# 8x8_LED_Anode_Driver_V3.net
KiCad netlist of a schematic drawn in EAGLE
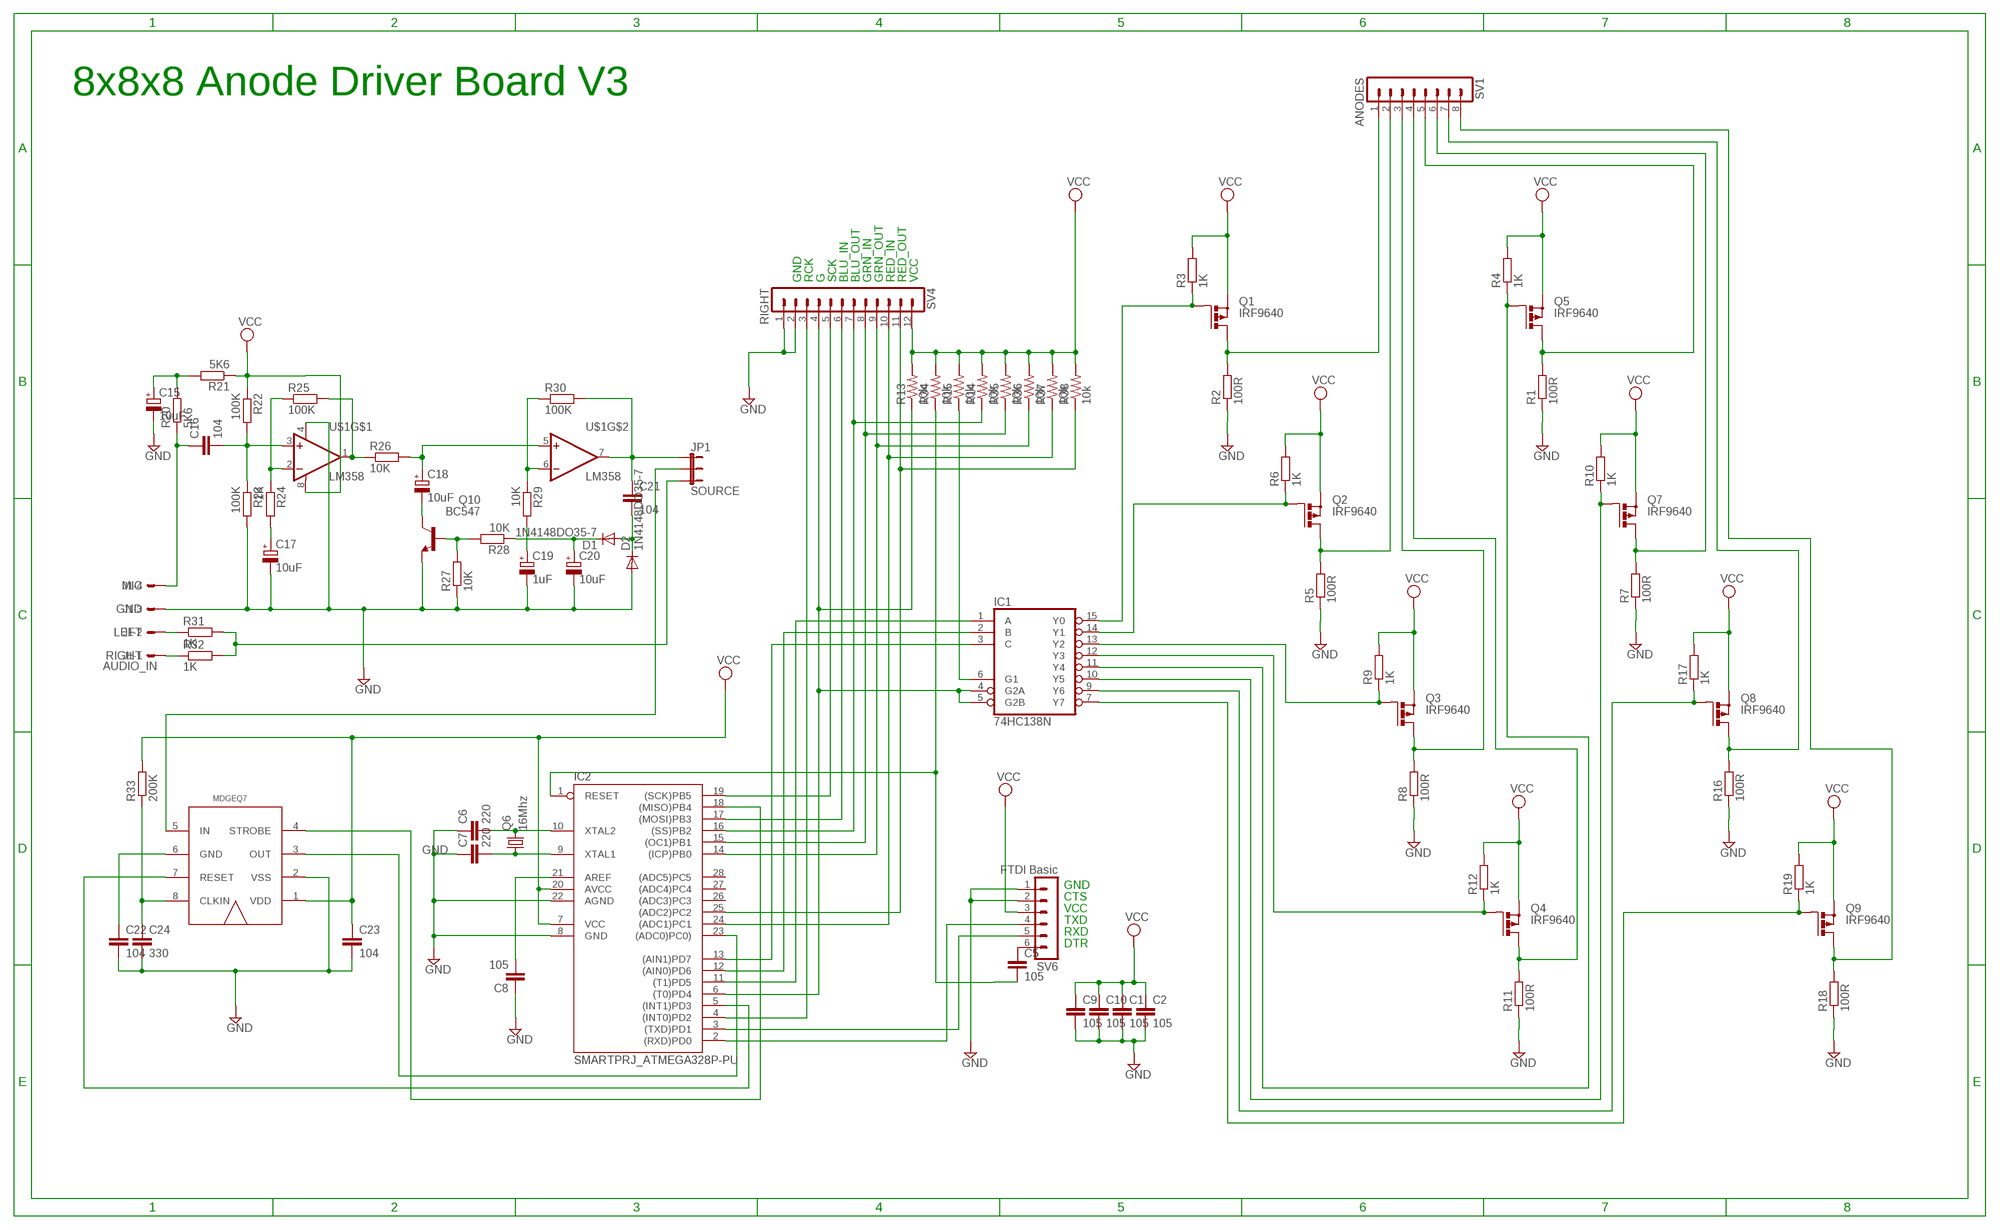
[diagram p0: schematic, sheet 1]

(export (version "E")
  (design (tool "Eeschema 10.0.6"))
  (components
    (comp (ref "C1")
      (value "105")
      (footprint "eagle-import:C025-030X050")
      (libsource (lib "eagle-import") (part "C-EU025-030X050"))
    )
    (comp (ref "C2")
      (value "105")
      (footprint "eagle-import:C025-030X050")
      (libsource (lib "eagle-import") (part "C-EU025-030X050"))
    )
    (comp (ref "C5")
      (value "105")
      (footprint "eagle-import:C050-025X075")
      (libsource (lib "eagle-import") (part "C-EU050-025X075"))
    )
    (comp (ref "C6")
      (value "220")
      (footprint "eagle-import:C050-025X075")
      (libsource (lib "eagle-import") (part "C-EU050-025X075"))
    )
    (comp (ref "C7")
      (value "220")
      (footprint "eagle-import:C050-025X075")
      (libsource (lib "eagle-import") (part "C-EU050-025X075"))
    )
    (comp (ref "C8")
      (value "105")
      (footprint "eagle-import:C025-025X050")
      (libsource (lib "eagle-import") (part "C-EU025-025X050"))
    )
    (comp (ref "C9")
      (value "105")
      (footprint "eagle-import:C025-025X050")
      (libsource (lib "eagle-import") (part "C-EU025-025X050"))
    )
    (comp (ref "C10")
      (value "105")
      (footprint "eagle-import:C025-030X050")
      (libsource (lib "eagle-import") (part "C-EU025-030X050"))
    )
    (comp (ref "C15")
      (value "10uF")
      (footprint "eagle-import:E2,5-5")
      (libsource (lib "eagle-import") (part "CPOL-EUE2.5-5"))
    )
    (comp (ref "C16")
      (value "104")
      (footprint "eagle-import:C050-030X075")
      (libsource (lib "eagle-import") (part "C-EU050-030X075"))
    )
    (comp (ref "C17")
      (value "10uF")
      (footprint "eagle-import:E2,5-5")
      (libsource (lib "eagle-import") (part "CPOL-EUE2.5-5"))
    )
    (comp (ref "C18")
      (value "10uF")
      (footprint "eagle-import:E2,5-5")
      (libsource (lib "eagle-import") (part "CPOL-EUE2.5-5"))
    )
    (comp (ref "C19")
      (value "1uF")
      (footprint "eagle-import:E2,5-5")
      (libsource (lib "eagle-import") (part "CPOL-EUE2.5-5"))
    )
    (comp (ref "C20")
      (value "10uF")
      (footprint "eagle-import:E2,5-5")
      (libsource (lib "eagle-import") (part "CPOL-EUE2.5-5"))
    )
    (comp (ref "C21")
      (value "104")
      (footprint "eagle-import:C050-030X075")
      (libsource (lib "eagle-import") (part "C-EU050-030X075"))
    )
    (comp (ref "C22")
      (value "104")
      (footprint "eagle-import:C025-030X050")
      (libsource (lib "eagle-import") (part "C-EU025-030X050"))
    )
    (comp (ref "C23")
      (value "104")
      (footprint "eagle-import:C025-030X050")
      (libsource (lib "eagle-import") (part "C-EU025-030X050"))
    )
    (comp (ref "C24")
      (value "330")
      (footprint "eagle-import:C050-030X075")
      (libsource (lib "eagle-import") (part "C-EU050-030X075"))
    )
    (comp (ref "D1")
      (value "1N4148DO35-7")
      (footprint "eagle-import:DO35-7")
      (libsource (lib "eagle-import") (part "1N4148DO35-7"))
    )
    (comp (ref "D2")
      (value "1N4148DO35-7")
      (footprint "eagle-import:DO35-7")
      (libsource (lib "eagle-import") (part "1N4148DO35-7"))
    )
    (comp (ref "IC1")
      (value "74HC138N")
      (footprint "eagle-import:DIL16")
      (libsource (lib "eagle-import") (part "74138NHC"))
    )
    (comp (ref "IC2")
      (value "SMARTPRJ_ATMEGA328P-PU")
      (footprint "eagle-import:SMARTPRJ_DIL28-3")
      (libsource (lib "eagle-import") (part "SMARTPRJ_ATMEGA328P-PU"))
    )
    (comp (ref "J1")
      (value "AUDIO_IN")
      (footprint "eagle-import:7395-04")
      (libsource (lib "eagle-import") (part "22-?-0405-7048"))
    )
    (comp (ref "JP1")
      (value "SOURCE")
      (footprint "eagle-import:1X03")
      (libsource (lib "eagle-import") (part "JUMPER-3PTH"))
    )
    (comp (ref "Q1")
      (value "IRF9640")
      (footprint "eagle-import:TO220BH_NO_HOLE")
      (libsource (lib "eagle-import") (part "PMOSFET_PTO220BH_NH"))
    )
    (comp (ref "Q2")
      (value "IRF9640")
      (footprint "eagle-import:TO220BH_NO_HOLE")
      (libsource (lib "eagle-import") (part "PMOSFET_PTO220BH_NH"))
    )
    (comp (ref "Q3")
      (value "IRF9640")
      (footprint "eagle-import:TO220BH_NO_HOLE")
      (libsource (lib "eagle-import") (part "PMOSFET_PTO220BH_NH"))
    )
    (comp (ref "Q4")
      (value "IRF9640")
      (footprint "eagle-import:TO220BH_NO_HOLE")
      (libsource (lib "eagle-import") (part "PMOSFET_PTO220BH_NH"))
    )
    (comp (ref "Q5")
      (value "IRF9640")
      (footprint "eagle-import:TO220BH_NO_HOLE")
      (libsource (lib "eagle-import") (part "PMOSFET_PTO220BH_NH"))
    )
    (comp (ref "Q6")
      (value "16Mhz")
      (footprint "eagle-import:HC49_S")
      (libsource (lib "eagle-import") (part "CRYSTALHC49S"))
    )
    (comp (ref "Q7")
      (value "IRF9640")
      (footprint "eagle-import:TO220BH_NO_HOLE")
      (libsource (lib "eagle-import") (part "PMOSFET_PTO220BH_NH"))
    )
    (comp (ref "Q8")
      (value "IRF9640")
      (footprint "eagle-import:TO220BH_NO_HOLE")
      (libsource (lib "eagle-import") (part "PMOSFET_PTO220BH_NH"))
    )
    (comp (ref "Q9")
      (value "IRF9640")
      (footprint "eagle-import:TO220BH_NO_HOLE")
      (libsource (lib "eagle-import") (part "PMOSFET_PTO220BH_NH"))
    )
    (comp (ref "Q10")
      (value "BC547")
      (footprint "eagle-import:TO92")
      (libsource (lib "eagle-import") (part "BC547"))
    )
    (comp (ref "R1")
      (value "100R")
      (footprint "eagle-import:0207_10")
      (libsource (lib "eagle-import") (part "R-EU_0207/10"))
    )
    (comp (ref "R2")
      (value "100R")
      (footprint "eagle-import:0207_10")
      (libsource (lib "eagle-import") (part "R-EU_0207/10"))
    )
    (comp (ref "R3")
      (value "1K")
      (footprint "eagle-import:0207_10")
      (libsource (lib "eagle-import") (part "R-EU_0207/10"))
    )
    (comp (ref "R4")
      (value "1K")
      (footprint "eagle-import:0207_10")
      (libsource (lib "eagle-import") (part "R-EU_0207/10"))
    )
    (comp (ref "R5")
      (value "100R")
      (footprint "eagle-import:0207_10")
      (libsource (lib "eagle-import") (part "R-EU_0207/10"))
    )
    (comp (ref "R6")
      (value "1K")
      (footprint "eagle-import:0207_10")
      (libsource (lib "eagle-import") (part "R-EU_0207/10"))
    )
    (comp (ref "R7")
      (value "100R")
      (footprint "eagle-import:0207_10")
      (libsource (lib "eagle-import") (part "R-EU_0207/10"))
    )
    (comp (ref "R8")
      (value "100R")
      (footprint "eagle-import:0207_10")
      (libsource (lib "eagle-import") (part "R-EU_0207/10"))
    )
    (comp (ref "R9")
      (value "1K")
      (footprint "eagle-import:0207_10")
      (libsource (lib "eagle-import") (part "R-EU_0207/10"))
    )
    (comp (ref "R10")
      (value "1K")
      (footprint "eagle-import:0207_10")
      (libsource (lib "eagle-import") (part "R-EU_0207/10"))
    )
    (comp (ref "R11")
      (value "100R")
      (footprint "eagle-import:0207_10")
      (libsource (lib "eagle-import") (part "R-EU_0207/10"))
    )
    (comp (ref "R12")
      (value "1K")
      (footprint "eagle-import:0207_10")
      (libsource (lib "eagle-import") (part "R-EU_0207/10"))
    )
    (comp (ref "R13")
      (value "10k")
      (footprint "eagle-import:0207_10")
      (libsource (lib "eagle-import") (part "R-US_0207/10"))
    )
    (comp (ref "R14")
      (value "10k")
      (footprint "eagle-import:0207_10")
      (libsource (lib "eagle-import") (part "R-US_0207/10"))
    )
    (comp (ref "R15")
      (value "10k")
      (footprint "eagle-import:0207_10")
      (libsource (lib "eagle-import") (part "R-US_0207/10"))
    )
    (comp (ref "R16")
      (value "100R")
      (footprint "eagle-import:0207_10")
      (libsource (lib "eagle-import") (part "R-EU_0207/10"))
    )
    (comp (ref "R17")
      (value "1K")
      (footprint "eagle-import:0207_10")
      (libsource (lib "eagle-import") (part "R-EU_0207/10"))
    )
    (comp (ref "R18")
      (value "100R")
      (footprint "eagle-import:0207_10")
      (libsource (lib "eagle-import") (part "R-EU_0207/10"))
    )
    (comp (ref "R19")
      (value "1K")
      (footprint "eagle-import:0207_10")
      (libsource (lib "eagle-import") (part "R-EU_0207/10"))
    )
    (comp (ref "R20")
      (value "5K6")
      (footprint "eagle-import:0207_10")
      (libsource (lib "eagle-import") (part "R-EU_0207/10"))
    )
    (comp (ref "R21")
      (value "5K6")
      (footprint "eagle-import:0207_10")
      (libsource (lib "eagle-import") (part "R-EU_0207/10"))
    )
    (comp (ref "R22")
      (value "100K")
      (footprint "eagle-import:0207_10")
      (libsource (lib "eagle-import") (part "R-EU_0207/10"))
    )
    (comp (ref "R23")
      (value "100K")
      (footprint "eagle-import:0207_10")
      (libsource (lib "eagle-import") (part "R-EU_0207/10"))
    )
    (comp (ref "R24")
      (value "1K")
      (footprint "eagle-import:0207_10")
      (libsource (lib "eagle-import") (part "R-EU_0207/10"))
    )
    (comp (ref "R25")
      (value "100K")
      (footprint "eagle-import:0207_10")
      (libsource (lib "eagle-import") (part "R-EU_0207/10"))
    )
    (comp (ref "R26")
      (value "10K")
      (footprint "eagle-import:0207_10")
      (libsource (lib "eagle-import") (part "R-EU_0207/10"))
    )
    (comp (ref "R27")
      (value "10K")
      (footprint "eagle-import:0207_10")
      (libsource (lib "eagle-import") (part "R-EU_0207/10"))
    )
    (comp (ref "R28")
      (value "10K")
      (footprint "eagle-import:0207_10")
      (libsource (lib "eagle-import") (part "R-EU_0207/10"))
    )
    (comp (ref "R29")
      (value "10K")
      (footprint "eagle-import:0207_10")
      (libsource (lib "eagle-import") (part "R-EU_0207/10"))
    )
    (comp (ref "R30")
      (value "100K")
      (footprint "eagle-import:0207_10")
      (libsource (lib "eagle-import") (part "R-EU_0207/10"))
    )
    (comp (ref "R31")
      (value "1K")
      (footprint "eagle-import:0207_10")
      (libsource (lib "eagle-import") (part "R-EU_0207/10"))
    )
    (comp (ref "R32")
      (value "1K")
      (footprint "eagle-import:0207_10")
      (libsource (lib "eagle-import") (part "R-EU_0207/10"))
    )
    (comp (ref "R33")
      (value "200K")
      (footprint "eagle-import:0207_10")
      (libsource (lib "eagle-import") (part "R-EU_0207/10"))
    )
    (comp (ref "R34")
      (value "10k")
      (footprint "eagle-import:0207_10")
      (libsource (lib "eagle-import") (part "R-US_0207/10"))
    )
    (comp (ref "R35")
      (value "10k")
      (footprint "eagle-import:0207_10")
      (libsource (lib "eagle-import") (part "R-US_0207/10"))
    )
    (comp (ref "R36")
      (value "10k")
      (footprint "eagle-import:0207_10")
      (libsource (lib "eagle-import") (part "R-US_0207/10"))
    )
    (comp (ref "R37")
      (value "10k")
      (footprint "eagle-import:0207_10")
      (libsource (lib "eagle-import") (part "R-US_0207/10"))
    )
    (comp (ref "R38")
      (value "10k")
      (footprint "eagle-import:0207_10")
      (libsource (lib "eagle-import") (part "R-US_0207/10"))
    )
    (comp (ref "SV1")
      (value "ANODES")
      (footprint "eagle-import:MA08-1W")
      (libsource (lib "eagle-import") (part "MA08-1W"))
    )
    (comp (ref "SV4")
      (value "RIGHT")
      (footprint "eagle-import:MA12-1W")
      (libsource (lib "eagle-import") (part "MA12-1W"))
    )
    (comp (ref "SV6")
      (value "FTDI Basic")
      (footprint "eagle-import:MA06-1")
      (libsource (lib "eagle-import") (part "MA06-1"))
    )
    (comp (ref "U$1")
      (value "LM358")
      (footprint "eagle-import:DIP08")
      (libsource (lib "eagle-import") (part "LM358"))
    )
    (comp (ref "U$2")
      (value "MSGEQ7")
      (footprint "eagle-import:DIL08")
      (libsource (lib "eagle-import") (part "MSGEQ7"))
    )
  )
  (nets
    (net (code "1") (name "GND") (class "Default")
      (node (ref "C1") (pin "2") (pinfunction "2_2") (pintype "passive"))
      (node (ref "C10") (pin "2") (pinfunction "2_2") (pintype "passive"))
      (node (ref "C15") (pin "-") (pinfunction "-_-") (pintype "passive"))
      (node (ref "C17") (pin "-") (pinfunction "-_-") (pintype "passive"))
      (node (ref "C19") (pin "-") (pinfunction "-_-") (pintype "passive"))
      (node (ref "C2") (pin "2") (pinfunction "2_2") (pintype "passive"))
      (node (ref "C20") (pin "-") (pinfunction "-_-") (pintype "passive"))
      (node (ref "C22") (pin "2") (pinfunction "2_2") (pintype "passive"))
      (node (ref "C23") (pin "2") (pinfunction "2_2") (pintype "passive"))
      (node (ref "C24") (pin "2") (pinfunction "2_2") (pintype "passive"))
      (node (ref "C6") (pin "1") (pinfunction "1_1") (pintype "passive"))
      (node (ref "C7") (pin "1") (pinfunction "1_1") (pintype "passive"))
      (node (ref "C8") (pin "1") (pinfunction "1_1") (pintype "passive"))
      (node (ref "C9") (pin "2") (pinfunction "2_2") (pintype "passive"))
      (node (ref "D2") (pin "A") (pinfunction "A_A") (pintype "passive"))
      (node (ref "IC2") (pin "22") (pinfunction "AGND_22") (pintype "power_in"))
      (node (ref "IC2") (pin "8") (pinfunction "GND_8") (pintype "power_in"))
      (node (ref "J1") (pin "3") (pinfunction "S_3") (pintype "passive"))
      (node (ref "Q10") (pin "1") (pinfunction "E_1") (pintype "passive"))
      (node (ref "R1") (pin "1") (pinfunction "1_1") (pintype "passive"))
      (node (ref "R11") (pin "1") (pinfunction "1_1") (pintype "passive"))
      (node (ref "R16") (pin "1") (pinfunction "1_1") (pintype "passive"))
      (node (ref "R18") (pin "1") (pinfunction "1_1") (pintype "passive"))
      (node (ref "R2") (pin "1") (pinfunction "1_1") (pintype "passive"))
      (node (ref "R23") (pin "2") (pinfunction "2_2") (pintype "passive"))
      (node (ref "R27") (pin "1") (pinfunction "1_1") (pintype "passive"))
      (node (ref "R5") (pin "1") (pinfunction "1_1") (pintype "passive"))
      (node (ref "R7") (pin "1") (pinfunction "1_1") (pintype "passive"))
      (node (ref "R8") (pin "1") (pinfunction "1_1") (pintype "passive"))
      (node (ref "SV4") (pin "1") (pinfunction "1_1") (pintype "passive"))
      (node (ref "SV4") (pin "2") (pinfunction "2_2") (pintype "passive"))
      (node (ref "SV6") (pin "1") (pinfunction "1_1") (pintype "passive"))
      (node (ref "SV6") (pin "2") (pinfunction "2_2") (pintype "passive"))
      (node (ref "U$1") (pin "4") (pinfunction "V-_4") (pintype "power_in"))
      (node (ref "U$2") (pin "2") (pinfunction "VSS_2") (pintype "power_in"))
    )
    (net (code "2") (name "Net-(C5-Pad1)") (class "Default")
      (node (ref "C5") (pin "1") (pinfunction "1_1") (pintype "passive"))
      (node (ref "SV6") (pin "6") (pinfunction "6_6") (pintype "passive"))
    )
    (net (code "3") (name "Net-(C15-Pad+)") (class "Default")
      (node (ref "C15") (pin "+") (pinfunction "+_+") (pintype "passive"))
      (node (ref "R20") (pin "2") (pinfunction "2_2") (pintype "passive"))
      (node (ref "R21") (pin "2") (pinfunction "2_2") (pintype "passive"))
    )
    (net (code "4") (name "Net-(C17-Pad+)") (class "Default")
      (node (ref "C17") (pin "+") (pinfunction "+_+") (pintype "passive"))
      (node (ref "R24") (pin "2") (pinfunction "2_2") (pintype "passive"))
    )
    (net (code "5") (name "Net-(C19-Pad+)") (class "Default")
      (node (ref "C19") (pin "+") (pinfunction "+_+") (pintype "passive"))
      (node (ref "R29") (pin "2") (pinfunction "2_2") (pintype "passive"))
    )
    (net (code "6") (name "Net-(C20-Pad+)") (class "Default")
      (node (ref "C20") (pin "+") (pinfunction "+_+") (pintype "passive"))
      (node (ref "D1") (pin "C") (pinfunction "C_C") (pintype "passive"))
      (node (ref "R28") (pin "1") (pinfunction "1_1") (pintype "passive"))
    )
    (net (code "7") (name "Net-(C21-Pad2)") (class "Default")
      (node (ref "C21") (pin "2") (pinfunction "2_2") (pintype "passive"))
      (node (ref "D1") (pin "A") (pinfunction "A_A") (pintype "passive"))
      (node (ref "D2") (pin "C") (pinfunction "C_C") (pintype "passive"))
    )
    (net (code "8") (name "Net-(IC1A-A)") (class "Default")
      (node (ref "IC1") (pin "1") (pinfunction "A_1") (pintype "input"))
      (node (ref "IC2") (pin "11") (pinfunction "(T1)PD5_11") (pintype "bidirectional"))
    )
    (net (code "9") (name "Net-(IC1A-B)") (class "Default")
      (node (ref "IC1") (pin "2") (pinfunction "B_2") (pintype "input"))
      (node (ref "IC2") (pin "12") (pinfunction "(AIN0)PD6_12") (pintype "bidirectional"))
    )
    (net (code "10") (name "Net-(IC1A-C)") (class "Default")
      (node (ref "IC1") (pin "3") (pinfunction "C_3") (pintype "input"))
      (node (ref "IC2") (pin "13") (pinfunction "(AIN1)PD7_13") (pintype "bidirectional"))
    )
    (net (code "11") (name "Net-(IC1A-G1)") (class "Default")
      (node (ref "IC1") (pin "6") (pinfunction "G1_6") (pintype "input"))
      (node (ref "R15") (pin "1") (pinfunction "1_1") (pintype "passive"))
    )
    (net (code "12") (name "Net-(IC1A-G2A)") (class "Default")
      (node (ref "IC1") (pin "4") (pinfunction "G2A_4") (pintype "input"))
      (node (ref "IC1") (pin "5") (pinfunction "G2B_5") (pintype "input"))
      (node (ref "IC2") (pin "6") (pinfunction "(T0)PD4_6") (pintype "bidirectional"))
      (node (ref "R13") (pin "1") (pinfunction "1_1") (pintype "passive"))
      (node (ref "SV4") (pin "4") (pinfunction "4_4") (pintype "passive"))
    )
    (net (code "13") (name "Net-(IC1A-Y0)") (class "Default")
      (node (ref "IC1") (pin "15") (pinfunction "Y0_15") (pintype "output"))
      (node (ref "Q1") (pin "G") (pinfunction "G_G") (pintype "passive"))
      (node (ref "R3") (pin "1") (pinfunction "1_1") (pintype "passive"))
    )
    (net (code "14") (name "Net-(IC1A-Y1)") (class "Default")
      (node (ref "IC1") (pin "14") (pinfunction "Y1_14") (pintype "output"))
      (node (ref "Q2") (pin "G") (pinfunction "G_G") (pintype "passive"))
      (node (ref "R6") (pin "1") (pinfunction "1_1") (pintype "passive"))
    )
    (net (code "15") (name "Net-(IC1A-Y2)") (class "Default")
      (node (ref "IC1") (pin "13") (pinfunction "Y2_13") (pintype "output"))
      (node (ref "Q3") (pin "G") (pinfunction "G_G") (pintype "passive"))
      (node (ref "R9") (pin "1") (pinfunction "1_1") (pintype "passive"))
    )
    (net (code "16") (name "Net-(IC1A-Y3)") (class "Default")
      (node (ref "IC1") (pin "12") (pinfunction "Y3_12") (pintype "output"))
      (node (ref "Q4") (pin "G") (pinfunction "G_G") (pintype "passive"))
      (node (ref "R12") (pin "1") (pinfunction "1_1") (pintype "passive"))
    )
    (net (code "17") (name "Net-(IC1A-Y4)") (class "Default")
      (node (ref "IC1") (pin "11") (pinfunction "Y4_11") (pintype "output"))
      (node (ref "Q5") (pin "G") (pinfunction "G_G") (pintype "passive"))
      (node (ref "R4") (pin "1") (pinfunction "1_1") (pintype "passive"))
    )
    (net (code "18") (name "Net-(IC1A-Y5)") (class "Default")
      (node (ref "IC1") (pin "10") (pinfunction "Y5_10") (pintype "output"))
      (node (ref "Q7") (pin "G") (pinfunction "G_G") (pintype "passive"))
      (node (ref "R10") (pin "1") (pinfunction "1_1") (pintype "passive"))
    )
    (net (code "19") (name "Net-(IC1A-Y6)") (class "Default")
      (node (ref "IC1") (pin "9") (pinfunction "Y6_9") (pintype "output"))
      (node (ref "Q8") (pin "G") (pinfunction "G_G") (pintype "passive"))
      (node (ref "R17") (pin "1") (pinfunction "1_1") (pintype "passive"))
    )
    (net (code "20") (name "Net-(IC1A-Y7)") (class "Default")
      (node (ref "IC1") (pin "7") (pinfunction "Y7_7") (pintype "output"))
      (node (ref "Q9") (pin "G") (pinfunction "G_G") (pintype "passive"))
      (node (ref "R19") (pin "1") (pinfunction "1_1") (pintype "passive"))
    )
    (net (code "21") (name "Net-(IC2-(ADC0)PC0))") (class "Default")
      (node (ref "IC2") (pin "23") (pinfunction "(ADC0)PC0)_23") (pintype "bidirectional"))
      (node (ref "U$2") (pin "3") (pinfunction "OUT_3") (pintype "output"))
    )
    (net (code "22") (name "Net-(IC2-(ADC1)PC1)") (class "Default")
      (node (ref "IC2") (pin "24") (pinfunction "(ADC1)PC1_24") (pintype "bidirectional"))
      (node (ref "R37") (pin "1") (pinfunction "1_1") (pintype "passive"))
      (node (ref "SV4") (pin "10") (pinfunction "10_10") (pintype "passive"))
    )
    (net (code "23") (name "Net-(IC2-(ADC2)PC2)") (class "Default")
      (node (ref "IC2") (pin "25") (pinfunction "(ADC2)PC2_25") (pintype "bidirectional"))
      (node (ref "R38") (pin "1") (pinfunction "1_1") (pintype "passive"))
      (node (ref "SV4") (pin "11") (pinfunction "11_11") (pintype "passive"))
    )
    (net (code "24") (name "Net-(IC2-(ICP)PB0)") (class "Default")
      (node (ref "IC2") (pin "14") (pinfunction "(ICP)PB0_14") (pintype "bidirectional"))
      (node (ref "R36") (pin "1") (pinfunction "1_1") (pintype "passive"))
      (node (ref "SV4") (pin "9") (pinfunction "9_9") (pintype "passive"))
    )
    (net (code "25") (name "Net-(IC2-(INT0)PD2)") (class "Default")
      (node (ref "IC2") (pin "4") (pinfunction "(INT0)PD2_4") (pintype "bidirectional"))
      (node (ref "SV4") (pin "3") (pinfunction "3_3") (pintype "passive"))
    )
    (net (code "26") (name "Net-(IC2-(INT1)PD3)") (class "Default")
      (node (ref "IC2") (pin "5") (pinfunction "(INT1)PD3_5") (pintype "bidirectional"))
      (node (ref "U$2") (pin "7") (pinfunction "RESET_7") (pintype "input"))
    )
    (net (code "27") (name "Net-(IC2-(MISO)PB4)") (class "Default")
      (node (ref "IC2") (pin "18") (pinfunction "(MISO)PB4_18") (pintype "bidirectional"))
      (node (ref "U$2") (pin "4") (pinfunction "STROBE_4") (pintype "input"))
    )
    (net (code "28") (name "Net-(IC2-(MOSI)PB3)") (class "Default")
      (node (ref "IC2") (pin "17") (pinfunction "(MOSI)PB3_17") (pintype "bidirectional"))
      (node (ref "SV4") (pin "6") (pinfunction "6_6") (pintype "passive"))
    )
    (net (code "29") (name "Net-(IC2-(OC1)PB1)") (class "Default")
      (node (ref "IC2") (pin "15") (pinfunction "(OC1)PB1_15") (pintype "bidirectional"))
      (node (ref "R35") (pin "1") (pinfunction "1_1") (pintype "passive"))
      (node (ref "SV4") (pin "8") (pinfunction "8_8") (pintype "passive"))
    )
    (net (code "30") (name "Net-(IC2-(RXD)PD0)") (class "Default")
      (node (ref "IC2") (pin "2") (pinfunction "(RXD)PD0_2") (pintype "bidirectional"))
      (node (ref "SV6") (pin "4") (pinfunction "4_4") (pintype "passive"))
    )
    (net (code "31") (name "Net-(IC2-(SCK)PB5)") (class "Default")
      (node (ref "IC2") (pin "19") (pinfunction "(SCK)PB5_19") (pintype "bidirectional"))
      (node (ref "SV4") (pin "5") (pinfunction "5_5") (pintype "passive"))
    )
    (net (code "32") (name "Net-(IC2-(SS)PB2)") (class "Default")
      (node (ref "IC2") (pin "16") (pinfunction "(SS)PB2_16") (pintype "bidirectional"))
      (node (ref "R14") (pin "1") (pinfunction "1_1") (pintype "passive"))
      (node (ref "SV4") (pin "7") (pinfunction "7_7") (pintype "passive"))
    )
    (net (code "33") (name "Net-(IC2-(TXD)PD1)") (class "Default")
      (node (ref "IC2") (pin "3") (pinfunction "(TXD)PD1_3") (pintype "bidirectional"))
      (node (ref "SV6") (pin "5") (pinfunction "5_5") (pintype "passive"))
    )
    (net (code "34") (name "Net-(IC2-AREF)") (class "Default")
      (node (ref "C8") (pin "2") (pinfunction "2_2") (pintype "passive"))
      (node (ref "IC2") (pin "21") (pinfunction "AREF_21") (pintype "passive"))
    )
    (net (code "35") (name "Net-(IC2-RESET)") (class "Default")
      (node (ref "C5") (pin "2") (pinfunction "2_2") (pintype "passive"))
      (node (ref "IC2") (pin "1") (pinfunction "RESET_1") (pintype "input"))
      (node (ref "R34") (pin "1") (pinfunction "1_1") (pintype "passive"))
    )
    (net (code "36") (name "Net-(IC2-XTAL1)") (class "Default")
      (node (ref "C7") (pin "2") (pinfunction "2_2") (pintype "passive"))
      (node (ref "IC2") (pin "9") (pinfunction "XTAL1_9") (pintype "bidirectional"))
      (node (ref "Q6") (pin "1") (pinfunction "1_1") (pintype "passive"))
    )
    (net (code "37") (name "Net-(IC2-XTAL2)") (class "Default")
      (node (ref "C6") (pin "2") (pinfunction "2_2") (pintype "passive"))
      (node (ref "IC2") (pin "10") (pinfunction "XTAL2_10") (pintype "bidirectional"))
      (node (ref "Q6") (pin "2") (pinfunction "2_2") (pintype "passive"))
    )
    (net (code "38") (name "Net-(J1A-S)") (class "Default")
      (node (ref "J1") (pin "1") (pinfunction "S_1") (pintype "passive"))
      (node (ref "R32") (pin "1") (pinfunction "1_1") (pintype "passive"))
    )
    (net (code "39") (name "Net-(J1B-S)") (class "Default")
      (node (ref "J1") (pin "2") (pinfunction "S_2") (pintype "passive"))
      (node (ref "R31") (pin "1") (pinfunction "1_1") (pintype "passive"))
    )
    (net (code "40") (name "Net-(J1D-S)") (class "Default")
      (node (ref "C16") (pin "1") (pinfunction "1_1") (pintype "passive"))
      (node (ref "J1") (pin "4") (pinfunction "S_4") (pintype "passive"))
      (node (ref "R20") (pin "1") (pinfunction "1_1") (pintype "passive"))
    )
    (net (code "41") (name "Net-(JP1-Pad3)") (class "Default")
      (node (ref "JP1") (pin "3") (pinfunction "3_3") (pintype "passive"))
      (node (ref "R31") (pin "2") (pinfunction "2_2") (pintype "passive"))
      (node (ref "R32") (pin "2") (pinfunction "2_2") (pintype "passive"))
    )
    (net (code "42") (name "Net-(Q1-PadD)") (class "Default")
      (node (ref "Q1") (pin "D") (pinfunction "D_D") (pintype "passive"))
      (node (ref "R2") (pin "2") (pinfunction "2_2") (pintype "passive"))
      (node (ref "SV1") (pin "1") (pinfunction "1_1") (pintype "passive"))
    )
    (net (code "43") (name "Net-(Q2-PadD)") (class "Default")
      (node (ref "Q2") (pin "D") (pinfunction "D_D") (pintype "passive"))
      (node (ref "R5") (pin "2") (pinfunction "2_2") (pintype "passive"))
      (node (ref "SV1") (pin "2") (pinfunction "2_2") (pintype "passive"))
    )
    (net (code "44") (name "Net-(Q3-PadD)") (class "Default")
      (node (ref "Q3") (pin "D") (pinfunction "D_D") (pintype "passive"))
      (node (ref "R8") (pin "2") (pinfunction "2_2") (pintype "passive"))
      (node (ref "SV1") (pin "3") (pinfunction "3_3") (pintype "passive"))
    )
    (net (code "45") (name "Net-(Q4-PadD)") (class "Default")
      (node (ref "Q4") (pin "D") (pinfunction "D_D") (pintype "passive"))
      (node (ref "R11") (pin "2") (pinfunction "2_2") (pintype "passive"))
      (node (ref "SV1") (pin "4") (pinfunction "4_4") (pintype "passive"))
    )
    (net (code "46") (name "Net-(Q5-PadD)") (class "Default")
      (node (ref "Q5") (pin "D") (pinfunction "D_D") (pintype "passive"))
      (node (ref "R1") (pin "2") (pinfunction "2_2") (pintype "passive"))
      (node (ref "SV1") (pin "5") (pinfunction "5_5") (pintype "passive"))
    )
    (net (code "47") (name "Net-(Q7-PadD)") (class "Default")
      (node (ref "Q7") (pin "D") (pinfunction "D_D") (pintype "passive"))
      (node (ref "R7") (pin "2") (pinfunction "2_2") (pintype "passive"))
      (node (ref "SV1") (pin "6") (pinfunction "6_6") (pintype "passive"))
    )
    (net (code "48") (name "Net-(Q8-PadD)") (class "Default")
      (node (ref "Q8") (pin "D") (pinfunction "D_D") (pintype "passive"))
      (node (ref "R16") (pin "2") (pinfunction "2_2") (pintype "passive"))
      (node (ref "SV1") (pin "7") (pinfunction "7_7") (pintype "passive"))
    )
    (net (code "49") (name "Net-(Q9-PadD)") (class "Default")
      (node (ref "Q9") (pin "D") (pinfunction "D_D") (pintype "passive"))
      (node (ref "R18") (pin "2") (pinfunction "2_2") (pintype "passive"))
      (node (ref "SV1") (pin "8") (pinfunction "8_8") (pintype "passive"))
    )
    (net (code "50") (name "Net-(Q10-B)") (class "Default")
      (node (ref "Q10") (pin "2") (pinfunction "B_2") (pintype "passive"))
      (node (ref "R27") (pin "2") (pinfunction "2_2") (pintype "passive"))
      (node (ref "R28") (pin "2") (pinfunction "2_2") (pintype "passive"))
    )
    (net (code "51") (name "Net-(Q10-C)") (class "Default")
      (node (ref "C18") (pin "-") (pinfunction "-_-") (pintype "passive"))
      (node (ref "Q10") (pin "3") (pinfunction "C_3") (pintype "passive"))
    )
    (net (code "52") (name "Net-(U$1A-+IN)") (class "Default")
      (node (ref "C16") (pin "2") (pinfunction "2_2") (pintype "passive"))
      (node (ref "R22") (pin "2") (pinfunction "2_2") (pintype "passive"))
      (node (ref "R23") (pin "1") (pinfunction "1_1") (pintype "passive"))
      (node (ref "U$1") (pin "3") (pinfunction "+IN_3") (pintype "input"))
    )
    (net (code "53") (name "Net-(U$1A--IN)") (class "Default")
      (node (ref "R24") (pin "1") (pinfunction "1_1") (pintype "passive"))
      (node (ref "R25") (pin "1") (pinfunction "1_1") (pintype "passive"))
      (node (ref "U$1") (pin "2") (pinfunction "-IN_2") (pintype "input"))
    )
    (net (code "54") (name "Net-(U$1A-OUT)") (class "Default")
      (node (ref "R25") (pin "2") (pinfunction "2_2") (pintype "passive"))
      (node (ref "R26") (pin "1") (pinfunction "1_1") (pintype "passive"))
      (node (ref "U$1") (pin "1") (pinfunction "OUT_1") (pintype "output"))
    )
    (net (code "55") (name "Net-(U$1B-+IN)") (class "Default")
      (node (ref "C18") (pin "+") (pinfunction "+_+") (pintype "passive"))
      (node (ref "R26") (pin "2") (pinfunction "2_2") (pintype "passive"))
      (node (ref "U$1") (pin "5") (pinfunction "+IN_5") (pintype "input"))
    )
    (net (code "56") (name "Net-(U$1B--IN)") (class "Default")
      (node (ref "R29") (pin "1") (pinfunction "1_1") (pintype "passive"))
      (node (ref "R30") (pin "1") (pinfunction "1_1") (pintype "passive"))
      (node (ref "U$1") (pin "6") (pinfunction "-IN_6") (pintype "input"))
    )
    (net (code "57") (name "Net-(U$1B-OUT)") (class "Default")
      (node (ref "C21") (pin "1") (pinfunction "1_1") (pintype "passive"))
      (node (ref "JP1") (pin "1") (pinfunction "1_1") (pintype "passive"))
      (node (ref "R30") (pin "2") (pinfunction "2_2") (pintype "passive"))
      (node (ref "U$1") (pin "7") (pinfunction "OUT_7") (pintype "output"))
    )
    (net (code "58") (name "Net-(U$2-CLKIN)") (class "Default")
      (node (ref "C24") (pin "1") (pinfunction "1_1") (pintype "passive"))
      (node (ref "R33") (pin "1") (pinfunction "1_1") (pintype "passive"))
      (node (ref "U$2") (pin "8") (pinfunction "CLKIN_8") (pintype "input"))
    )
    (net (code "59") (name "Net-(U$2-GND)") (class "Default")
      (node (ref "C22") (pin "1") (pinfunction "1_1") (pintype "passive"))
      (node (ref "U$2") (pin "6") (pinfunction "GND_6") (pintype "bidirectional"))
    )
    (net (code "60") (name "Net-(U$2-IN)") (class "Default")
      (node (ref "JP1") (pin "2") (pinfunction "2_2") (pintype "passive"))
      (node (ref "U$2") (pin "5") (pinfunction "IN_5") (pintype "input"))
    )
    (net (code "61") (name "VCC") (class "Default")
      (node (ref "C1") (pin "1") (pinfunction "1_1") (pintype "passive"))
      (node (ref "C10") (pin "1") (pinfunction "1_1") (pintype "passive"))
      (node (ref "C2") (pin "1") (pinfunction "1_1") (pintype "passive"))
      (node (ref "C23") (pin "1") (pinfunction "1_1") (pintype "passive"))
      (node (ref "C9") (pin "1") (pinfunction "1_1") (pintype "passive"))
      (node (ref "IC2") (pin "20") (pinfunction "AVCC_20") (pintype "power_in"))
      (node (ref "IC2") (pin "7") (pinfunction "VCC_7") (pintype "power_in"))
      (node (ref "Q1") (pin "S") (pinfunction "S_S") (pintype "passive"))
      (node (ref "Q2") (pin "S") (pinfunction "S_S") (pintype "passive"))
      (node (ref "Q3") (pin "S") (pinfunction "S_S") (pintype "passive"))
      (node (ref "Q4") (pin "S") (pinfunction "S_S") (pintype "passive"))
      (node (ref "Q5") (pin "S") (pinfunction "S_S") (pintype "passive"))
      (node (ref "Q7") (pin "S") (pinfunction "S_S") (pintype "passive"))
      (node (ref "Q8") (pin "S") (pinfunction "S_S") (pintype "passive"))
      (node (ref "Q9") (pin "S") (pinfunction "S_S") (pintype "passive"))
      (node (ref "R10") (pin "2") (pinfunction "2_2") (pintype "passive"))
      (node (ref "R12") (pin "2") (pinfunction "2_2") (pintype "passive"))
      (node (ref "R13") (pin "2") (pinfunction "2_2") (pintype "passive"))
      (node (ref "R14") (pin "2") (pinfunction "2_2") (pintype "passive"))
      (node (ref "R15") (pin "2") (pinfunction "2_2") (pintype "passive"))
      (node (ref "R17") (pin "2") (pinfunction "2_2") (pintype "passive"))
      (node (ref "R19") (pin "2") (pinfunction "2_2") (pintype "passive"))
      (node (ref "R21") (pin "1") (pinfunction "1_1") (pintype "passive"))
      (node (ref "R22") (pin "1") (pinfunction "1_1") (pintype "passive"))
      (node (ref "R3") (pin "2") (pinfunction "2_2") (pintype "passive"))
      (node (ref "R33") (pin "2") (pinfunction "2_2") (pintype "passive"))
      (node (ref "R34") (pin "2") (pinfunction "2_2") (pintype "passive"))
      (node (ref "R35") (pin "2") (pinfunction "2_2") (pintype "passive"))
      (node (ref "R36") (pin "2") (pinfunction "2_2") (pintype "passive"))
      (node (ref "R37") (pin "2") (pinfunction "2_2") (pintype "passive"))
      (node (ref "R38") (pin "2") (pinfunction "2_2") (pintype "passive"))
      (node (ref "R4") (pin "2") (pinfunction "2_2") (pintype "passive"))
      (node (ref "R6") (pin "2") (pinfunction "2_2") (pintype "passive"))
      (node (ref "R9") (pin "2") (pinfunction "2_2") (pintype "passive"))
      (node (ref "SV4") (pin "12") (pinfunction "12_12") (pintype "passive"))
      (node (ref "SV6") (pin "3") (pinfunction "3_3") (pintype "passive"))
      (node (ref "U$1") (pin "8") (pinfunction "V+_8") (pintype "power_in"))
      (node (ref "U$2") (pin "1") (pinfunction "VDD_1") (pintype "power_in"))
    )
    (net (code "62") (name "unconnected-(IC2-(ADC3)PC3-Pad26)") (class "Default")
      (node (ref "IC2") (pin "26") (pinfunction "(ADC3)PC3_26") (pintype "bidirectional"))
    )
    (net (code "63") (name "unconnected-(IC2-(ADC4)PC4-Pad27)") (class "Default")
      (node (ref "IC2") (pin "27") (pinfunction "(ADC4)PC4_27") (pintype "bidirectional"))
    )
    (net (code "64") (name "unconnected-(IC2-(ADC5)PC5-Pad28)") (class "Default")
      (node (ref "IC2") (pin "28") (pinfunction "(ADC5)PC5_28") (pintype "bidirectional"))
    )
  )
)
